# 485.net
KiCad netlist of a schematic drawn in Altium Designer
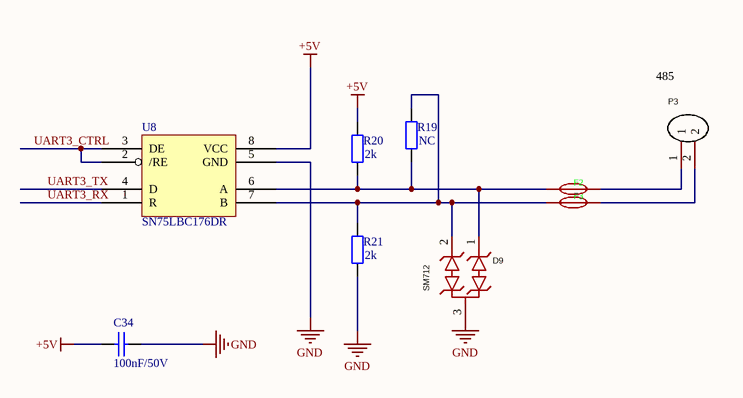
[diagram p0: 485.SchDoc]

(export (version "E")
  (design (tool "Eeschema 10.0.6"))
  (components
    (comp (ref "C34")
      (value "100nF/50V")
      (footprint "C-0805")
      (description "电容")
      (libsource (lib "泰开常用器件") (part "C普通电容"))
    )
    (comp (ref "D9")
      (value "SM712")
      (footprint "SOT-23-3")
      (fields (field (name "MANUFACTURER") "宏迦橙"))
      (libsource (lib "altium-import") (part "root_2_SM712_C7420375_"))
    )
    (comp (ref "F2")
      (value "SMD1206-020-48")
      (footprint "F1206")
      (fields (field (name "MANUFACTURER") "宏嘉诚"))
      (libsource (lib "altium-import") (part "root_0_SMD1206-020-48_"))
    )
    (comp (ref "F3")
      (value "SMD1206-020-48")
      (footprint "F1206")
      (fields (field (name "MANUFACTURER") "宏嘉诚"))
      (libsource (lib "altium-import") (part "root_0_SMD1206-020-48_"))
    )
    (comp (ref "P3")
      (value "WJ500V-5.08-2P")
      (footprint "KF128-2P DG128")
      (fields (field (name "MANUFACTURER") "KANGNEX(康奈克斯电气)"))
      (libsource (lib "泰开常用器件") (part "WJ500V-5.08-2P"))
    )
    (comp (ref "R19")
      (value "NC")
      (footprint "R-0805")
      (description "电阻")
      (fields (field (name "PUBLISHER") "Altium Limited"))
      (libsource (lib "泰开常用器件") (part "RES"))
    )
    (comp (ref "R20")
      (value "2k")
      (footprint "R-0805")
      (description "电阻")
      (fields (field (name "PUBLISHER") "Altium Limited"))
      (libsource (lib "泰开常用器件") (part "RES"))
    )
    (comp (ref "R21")
      (value "2k")
      (footprint "R-0805")
      (description "电阻")
      (fields (field (name "PUBLISHER") "Altium Limited"))
      (libsource (lib "泰开常用器件") (part "RES"))
    )
    (comp (ref "U8")
      (value "SN75LBC176DR")
      (footprint "SOP-8")
      (description "芯片")
      (libsource (lib "芯片") (part "75LBC176"))
    )
  )
  (nets
    (net (code "1") (name "+5V") (class "Default")
      (node (ref "C34") (pin "1") (pinfunction "1_1") (pintype "passive"))
      (node (ref "R20") (pin "2") (pinfunction "2_2") (pintype "passive"))
      (node (ref "U8") (pin "8") (pinfunction "VCC_8") (pintype "passive"))
    )
    (net (code "2") (name "/UART3_CTRL") (class "Default")
      (node (ref "U8") (pin "2") (pinfunction "/RE_2") (pintype "passive"))
      (node (ref "U8") (pin "3") (pinfunction "DE_3") (pintype "passive"))
    )
    (net (code "3") (name "/UART3_RX") (class "Default")
      (node (ref "U8") (pin "1") (pinfunction "R_1") (pintype "passive"))
    )
    (net (code "4") (name "/UART3_TX") (class "Default")
      (node (ref "U8") (pin "4") (pinfunction "D_4") (pintype "passive"))
    )
    (net (code "5") (name "GND") (class "Default")
      (node (ref "C34") (pin "2") (pinfunction "2_2") (pintype "passive"))
      (node (ref "D9") (pin "3") (pinfunction "3_3") (pintype "passive"))
      (node (ref "R21") (pin "1") (pinfunction "1_1") (pintype "passive"))
      (node (ref "U8") (pin "5") (pinfunction "GND_5") (pintype "passive"))
    )
    (net (code "6") (name "Net-(F2-Pad2)") (class "Default")
      (node (ref "F2") (pin "2") (pinfunction "2_2") (pintype "passive"))
      (node (ref "P3") (pin "1") (pinfunction "1_1") (pintype "passive"))
    )
    (net (code "7") (name "Net-(F3-Pad2)") (class "Default")
      (node (ref "F3") (pin "2") (pinfunction "2_2") (pintype "passive"))
      (node (ref "P3") (pin "2") (pinfunction "2_2") (pintype "passive"))
    )
    (net (code "8") (name "Net-(U8-A)") (class "Default")
      (node (ref "D9") (pin "1") (pinfunction "1_1") (pintype "passive"))
      (node (ref "F2") (pin "1") (pinfunction "1_1") (pintype "passive"))
      (node (ref "R19") (pin "1") (pinfunction "1_1") (pintype "passive"))
      (node (ref "R20") (pin "1") (pinfunction "1_1") (pintype "passive"))
      (node (ref "U8") (pin "6") (pinfunction "A_6") (pintype "passive"))
    )
    (net (code "9") (name "Net-(U8-B)") (class "Default")
      (node (ref "D9") (pin "2") (pinfunction "2_2") (pintype "passive"))
      (node (ref "F3") (pin "1") (pinfunction "1_1") (pintype "passive"))
      (node (ref "R19") (pin "2") (pinfunction "2_2") (pintype "passive"))
      (node (ref "R21") (pin "2") (pinfunction "2_2") (pintype "passive"))
      (node (ref "U8") (pin "7") (pinfunction "B_7") (pintype "passive"))
    )
  )
)
